# POTENTIAL_PCB.net
KiCad netlist of a schematic drawn in EasyEDA
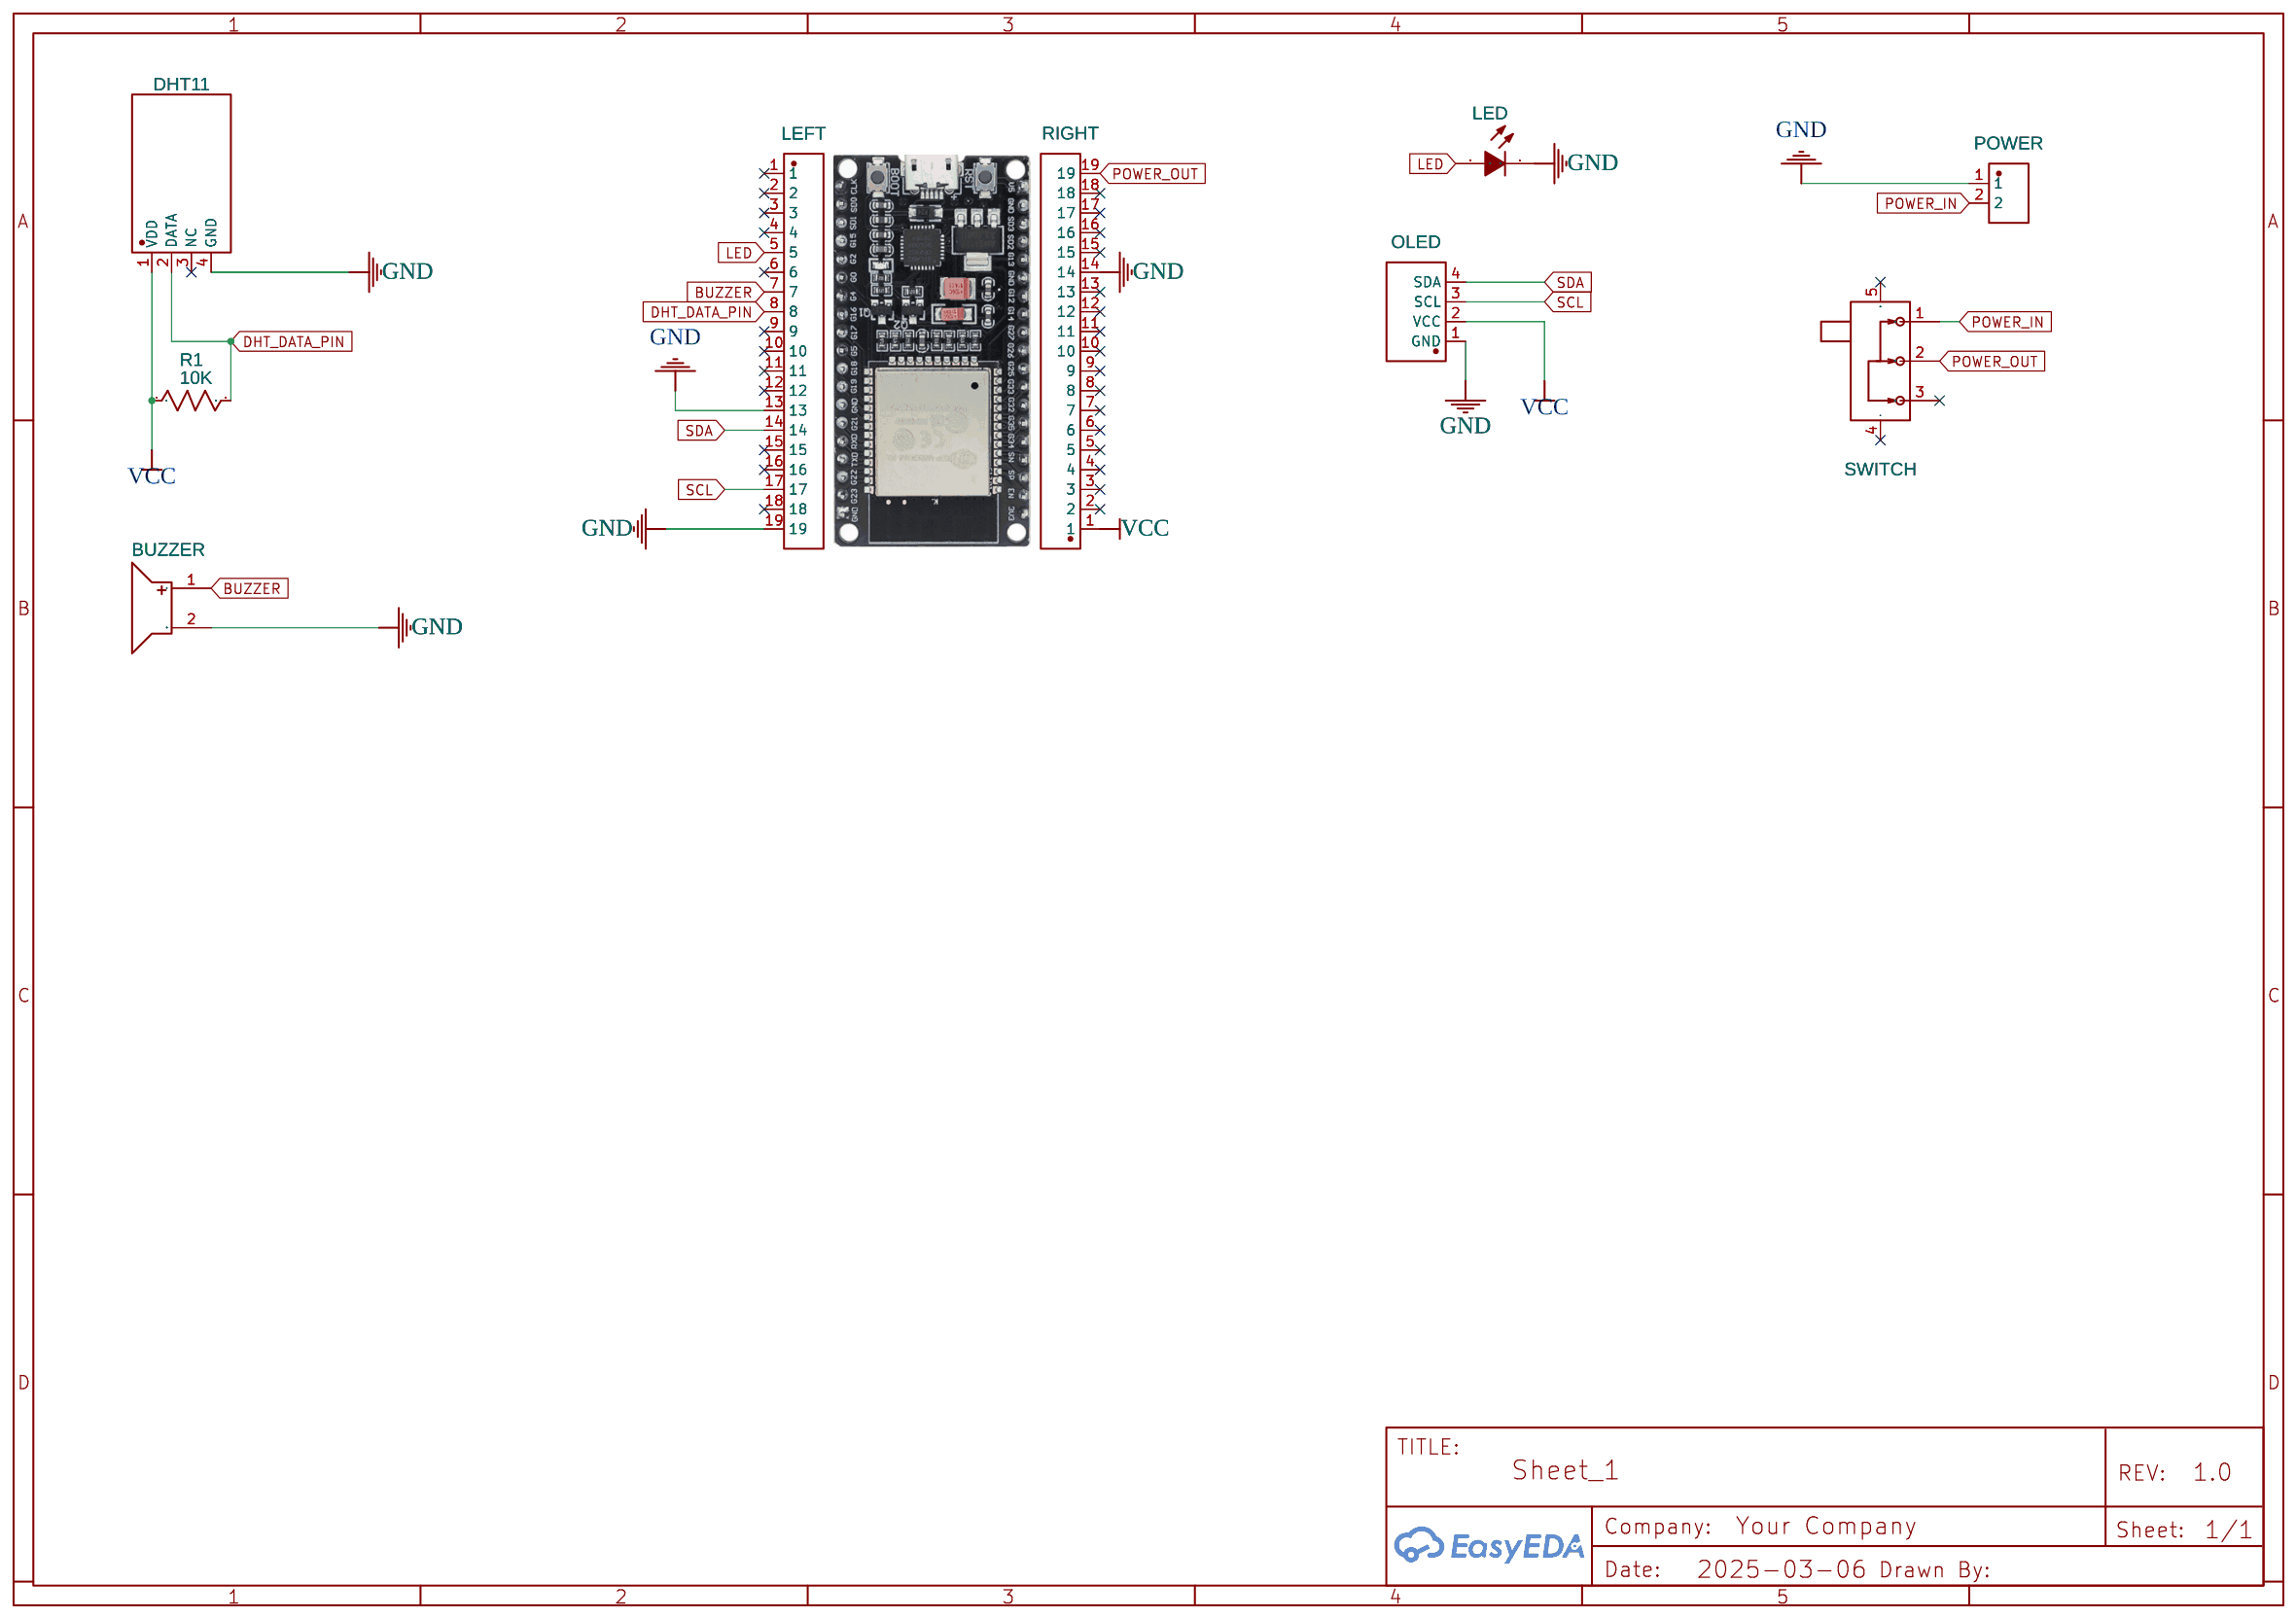
[diagram p0: schematic sheet]

(export (version "E")
  (design (tool "Eeschema 10.0.6"))
  (components
    (comp (ref "BUZZER1")
      (value "BUZZER")
      (fields (field (name "Manufacturer Part") "FS6737") (field (name "Manufacturer") "FUET(福声科技)"))
      (libsource (lib "") (part "FS6737"))
    )
    (comp (ref "DHT11")
      (value "DHT11")
      (fields (field (name "Manufacturer") "广州奥松"))
      (libsource (lib "") (part "DHT11"))
    )
    (comp (ref "LED")
      (value "LED")
      (fields
        (field (name "Manufacturer Part") "333-2SURD/S530-A3")
        (field (name "Manufacturer") "EVERLIGHT(亿光)")
      )
      (libsource (lib "") (part "333-2SURD/S530-A3"))
    )
    (comp (ref "LEFT")
      (value "2.54-1*19P母")
      (fields (field (name "Manufacturer") "BOOMELE(博穆精密)"))
      (libsource (lib "") (part "2.54-1*19P母_1"))
    )
    (comp (ref "OLED")
      (value "HS96L03W2C03")
      (fields (field (name "Manufacturer") "HS(汉昇)"))
      (libsource (lib "") (part "HS96L03W2C03"))
    )
    (comp (ref "POWER")
      (value "DB125-2.54-2P-GN")
      (fields
        (field (name "Manufacturer Part") "DB125-2.54-2P-GN-S")
        (field (name "Manufacturer") "DORABO(地博电气)")
      )
      (libsource (lib "") (part "DB125-2.54-2P-GN"))
    )
    (comp (ref "R1") (value "10K") (libsource (lib "") (part "R_0603_US")))
    (comp (ref "RIGHT")
      (value "2.54-1*19P母")
      (fields (field (name "Manufacturer") "BOOMELE(博穆精密)"))
      (libsource (lib "") (part "2.54-1*19P母"))
    )
    (comp (ref "SWITCH")
      (value "SS-12D11-G030")
      (fields (field (name "Manufacturer") "G-Switch(品赞)"))
      (libsource (lib "") (part "SS-12D11-G030"))
    )
  )
  (nets
    (net (code "1") (name "BUZZER") (class "Default")
      (node (ref "BUZZER1") (pin "1") (pinfunction "1_1") (pintype "unspecified"))
      (node (ref "LEFT") (pin "7") (pinfunction "7_7") (pintype "unspecified"))
    )
    (net (code "2") (name "DHT_DATA_PIN") (class "Default")
      (node (ref "DHT11") (pin "2") (pinfunction "DATA_2") (pintype "unspecified"))
      (node (ref "LEFT") (pin "8") (pinfunction "8_8") (pintype "unspecified"))
      (node (ref "R1") (pin "2") (pinfunction "2_2") (pintype "unspecified"))
    )
    (net (code "3") (name "GND") (class "Default")
      (node (ref "BUZZER1") (pin "2") (pinfunction "2_2") (pintype "unspecified"))
      (node (ref "DHT11") (pin "4") (pinfunction "GND_4") (pintype "unspecified"))
      (node (ref "LED") (pin "1") (pinfunction "C_1") (pintype "input"))
      (node (ref "LEFT") (pin "13") (pinfunction "13_13") (pintype "unspecified"))
      (node (ref "LEFT") (pin "19") (pinfunction "19_19") (pintype "unspecified"))
      (node (ref "OLED") (pin "1") (pinfunction "GND_1") (pintype "unspecified"))
      (node (ref "POWER") (pin "1") (pinfunction "1_1") (pintype "unspecified"))
      (node (ref "RIGHT") (pin "14") (pinfunction "14_14") (pintype "unspecified"))
    )
    (net (code "4") (name "LED") (class "Default")
      (node (ref "LED") (pin "2") (pinfunction "A_2") (pintype "input"))
      (node (ref "LEFT") (pin "5") (pinfunction "5_5") (pintype "unspecified"))
    )
    (net (code "5") (name "POWER_IN") (class "Default")
      (node (ref "POWER") (pin "2") (pinfunction "2_2") (pintype "unspecified"))
      (node (ref "SWITCH") (pin "1") (pinfunction "1_1") (pintype "unspecified"))
    )
    (net (code "6") (name "POWER_OUT") (class "Default")
      (node (ref "RIGHT") (pin "19") (pinfunction "19_19") (pintype "unspecified"))
      (node (ref "SWITCH") (pin "2") (pinfunction "2_2") (pintype "unspecified"))
    )
    (net (code "7") (name "SCL") (class "Default")
      (node (ref "LEFT") (pin "17") (pinfunction "17_17") (pintype "unspecified"))
      (node (ref "OLED") (pin "3") (pinfunction "SCL_3") (pintype "unspecified"))
    )
    (net (code "8") (name "SDA") (class "Default")
      (node (ref "LEFT") (pin "14") (pinfunction "14_14") (pintype "unspecified"))
      (node (ref "OLED") (pin "4") (pinfunction "SDA_4") (pintype "unspecified"))
    )
    (net (code "9") (name "VCC") (class "Default")
      (node (ref "DHT11") (pin "1") (pinfunction "VDD_1") (pintype "unspecified"))
      (node (ref "OLED") (pin "2") (pinfunction "VCC_2") (pintype "unspecified"))
      (node (ref "R1") (pin "1") (pinfunction "1_1") (pintype "unspecified"))
      (node (ref "RIGHT") (pin "1") (pinfunction "1_1") (pintype "unspecified"))
    )
    (net (code "10") (name "unconnected-(DHT11-NC-Pad3)") (class "Default")
      (node (ref "DHT11") (pin "3") (pinfunction "NC_3") (pintype "unspecified+no_connect"))
    )
    (net (code "11") (name "unconnected-(LEFT-Pad1)") (class "Default")
      (node (ref "LEFT") (pin "1") (pinfunction "1_1") (pintype "unspecified+no_connect"))
    )
    (net (code "12") (name "unconnected-(LEFT-Pad2)") (class "Default")
      (node (ref "LEFT") (pin "2") (pinfunction "2_2") (pintype "unspecified+no_connect"))
    )
    (net (code "13") (name "unconnected-(LEFT-Pad3)") (class "Default")
      (node (ref "LEFT") (pin "3") (pinfunction "3_3") (pintype "unspecified+no_connect"))
    )
    (net (code "14") (name "unconnected-(LEFT-Pad4)") (class "Default")
      (node (ref "LEFT") (pin "4") (pinfunction "4_4") (pintype "unspecified+no_connect"))
    )
    (net (code "15") (name "unconnected-(LEFT-Pad6)") (class "Default")
      (node (ref "LEFT") (pin "6") (pinfunction "6_6") (pintype "unspecified+no_connect"))
    )
    (net (code "16") (name "unconnected-(LEFT-Pad9)") (class "Default")
      (node (ref "LEFT") (pin "9") (pinfunction "9_9") (pintype "unspecified+no_connect"))
    )
    (net (code "17") (name "unconnected-(LEFT-Pad10)") (class "Default")
      (node (ref "LEFT") (pin "10") (pinfunction "10_10") (pintype "unspecified+no_connect"))
    )
    (net (code "18") (name "unconnected-(LEFT-Pad11)") (class "Default")
      (node (ref "LEFT") (pin "11") (pinfunction "11_11") (pintype "unspecified+no_connect"))
    )
    (net (code "19") (name "unconnected-(LEFT-Pad12)") (class "Default")
      (node (ref "LEFT") (pin "12") (pinfunction "12_12") (pintype "unspecified+no_connect"))
    )
    (net (code "20") (name "unconnected-(LEFT-Pad15)") (class "Default")
      (node (ref "LEFT") (pin "15") (pinfunction "15_15") (pintype "unspecified+no_connect"))
    )
    (net (code "21") (name "unconnected-(LEFT-Pad16)") (class "Default")
      (node (ref "LEFT") (pin "16") (pinfunction "16_16") (pintype "unspecified+no_connect"))
    )
    (net (code "22") (name "unconnected-(LEFT-Pad18)") (class "Default")
      (node (ref "LEFT") (pin "18") (pinfunction "18_18") (pintype "unspecified+no_connect"))
    )
    (net (code "23") (name "unconnected-(RIGHT-Pad2)") (class "Default")
      (node (ref "RIGHT") (pin "2") (pinfunction "2_2") (pintype "unspecified+no_connect"))
    )
    (net (code "24") (name "unconnected-(RIGHT-Pad3)") (class "Default")
      (node (ref "RIGHT") (pin "3") (pinfunction "3_3") (pintype "unspecified+no_connect"))
    )
    (net (code "25") (name "unconnected-(RIGHT-Pad4)") (class "Default")
      (node (ref "RIGHT") (pin "4") (pinfunction "4_4") (pintype "unspecified+no_connect"))
    )
    (net (code "26") (name "unconnected-(RIGHT-Pad5)") (class "Default")
      (node (ref "RIGHT") (pin "5") (pinfunction "5_5") (pintype "unspecified+no_connect"))
    )
    (net (code "27") (name "unconnected-(RIGHT-Pad6)") (class "Default")
      (node (ref "RIGHT") (pin "6") (pinfunction "6_6") (pintype "unspecified+no_connect"))
    )
    (net (code "28") (name "unconnected-(RIGHT-Pad7)") (class "Default")
      (node (ref "RIGHT") (pin "7") (pinfunction "7_7") (pintype "unspecified+no_connect"))
    )
    (net (code "29") (name "unconnected-(RIGHT-Pad8)") (class "Default")
      (node (ref "RIGHT") (pin "8") (pinfunction "8_8") (pintype "unspecified+no_connect"))
    )
    (net (code "30") (name "unconnected-(RIGHT-Pad9)") (class "Default")
      (node (ref "RIGHT") (pin "9") (pinfunction "9_9") (pintype "unspecified+no_connect"))
    )
    (net (code "31") (name "unconnected-(RIGHT-Pad10)") (class "Default")
      (node (ref "RIGHT") (pin "10") (pinfunction "10_10") (pintype "unspecified+no_connect"))
    )
    (net (code "32") (name "unconnected-(RIGHT-Pad11)") (class "Default")
      (node (ref "RIGHT") (pin "11") (pinfunction "11_11") (pintype "unspecified+no_connect"))
    )
    (net (code "33") (name "unconnected-(RIGHT-Pad12)") (class "Default")
      (node (ref "RIGHT") (pin "12") (pinfunction "12_12") (pintype "unspecified+no_connect"))
    )
    (net (code "34") (name "unconnected-(RIGHT-Pad13)") (class "Default")
      (node (ref "RIGHT") (pin "13") (pinfunction "13_13") (pintype "unspecified+no_connect"))
    )
    (net (code "35") (name "unconnected-(RIGHT-Pad15)") (class "Default")
      (node (ref "RIGHT") (pin "15") (pinfunction "15_15") (pintype "unspecified+no_connect"))
    )
    (net (code "36") (name "unconnected-(RIGHT-Pad16)") (class "Default")
      (node (ref "RIGHT") (pin "16") (pinfunction "16_16") (pintype "unspecified+no_connect"))
    )
    (net (code "37") (name "unconnected-(RIGHT-Pad17)") (class "Default")
      (node (ref "RIGHT") (pin "17") (pinfunction "17_17") (pintype "unspecified+no_connect"))
    )
    (net (code "38") (name "unconnected-(RIGHT-Pad18)") (class "Default")
      (node (ref "RIGHT") (pin "18") (pinfunction "18_18") (pintype "unspecified+no_connect"))
    )
    (net (code "39") (name "unconnected-(SWITCH-Pad3)") (class "Default")
      (node (ref "SWITCH") (pin "3") (pinfunction "3_3") (pintype "unspecified+no_connect"))
    )
    (net (code "40") (name "unconnected-(SWITCH-Pad4)") (class "Default")
      (node (ref "SWITCH") (pin "4") (pinfunction "4_4") (pintype "unspecified+no_connect"))
    )
    (net (code "41") (name "unconnected-(SWITCH-Pad5)") (class "Default")
      (node (ref "SWITCH") (pin "5") (pinfunction "5_5") (pintype "unspecified+no_connect"))
    )
  )
)
